# Proximity_sensor_v1.net
KiCad netlist of a schematic drawn in EAGLE
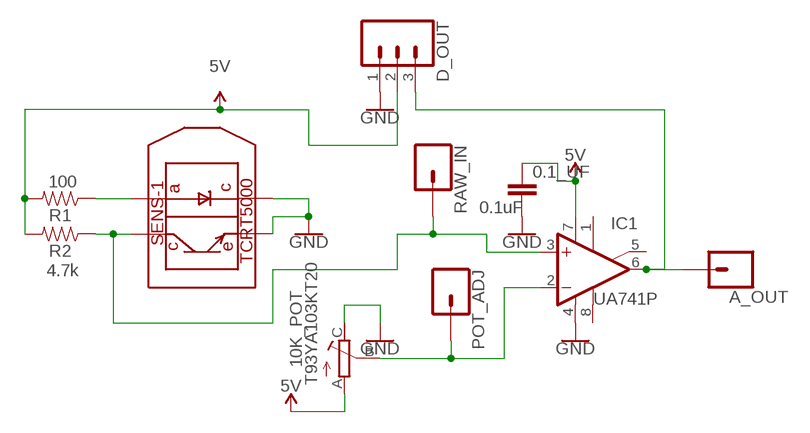
[diagram p0: schematic, sheet 1]

(export (version "E")
  (design (tool "Eeschema 10.0.6"))
  (components
    (comp (ref "0.1_UF")
      (value "0.1uF")
      (footprint "eagle-import:CAP-PTH-SMALL-KIT")
      (libsource (lib "eagle-import") (part "0.1UF-KIT-EZ-50V-20%"))
    )
    (comp (ref "10K_POT")
      (value "T93YA103KT20")
      (footprint "eagle-import:TRIM_T93YA103KT20")
      (fields (field (name "DIGI-KEY_PART_NUMBER") "T93YA-10K-ND") (field (name "MF") "Vishay"))
      (libsource (lib "eagle-import") (part "T93YA103KT20"))
    )
    (comp (ref "A_OUT")
      (value "CONN_01")
      (footprint "eagle-import:1X01")
      (libsource (lib "eagle-import") (part "CONN_01"))
    )
    (comp (ref "D_OUT")
      (value "CONN_03")
      (footprint "eagle-import:1X03")
      (libsource (lib "eagle-import") (part "CONN_03"))
    )
    (comp (ref "IC1")
      (value "UA741P")
      (footprint "eagle-import:DIL08")
      (libsource (lib "eagle-import") (part "741PUA"))
    )
    (comp (ref "POT_ADJ")
      (value "CONN_01")
      (footprint "eagle-import:1X01")
      (libsource (lib "eagle-import") (part "CONN_01"))
    )
    (comp (ref "R1")
      (value "100")
      (footprint "eagle-import:AXIAL-0.3-KIT")
      (libsource (lib "eagle-import") (part "RESISTORAXIAL-0.3-KIT"))
    )
    (comp (ref "R2")
      (value "4.7k")
      (footprint "eagle-import:AXIAL-0.3-KIT")
      (libsource (lib "eagle-import") (part "RESISTORAXIAL-0.3-KIT"))
    )
    (comp (ref "RAW_IN")
      (value "CONN_01")
      (footprint "eagle-import:1X01")
      (libsource (lib "eagle-import") (part "CONN_01"))
    )
    (comp (ref "SENS-1")
      (value "TCRT5000")
      (footprint "eagle-import:5000")
      (libsource (lib "eagle-import") (part "TCRT5000"))
    )
  )
  (nets
    (net (code "1") (name "5V") (class "Default")
      (node (ref "0.1_UF") (pin "1") (pinfunction "1_1") (pintype "passive"))
      (node (ref "10K_POT") (pin "A") (pinfunction "A_A") (pintype "passive"))
      (node (ref "D_OUT") (pin "2") (pinfunction "2_2") (pintype "passive"))
      (node (ref "IC1") (pin "7") (pinfunction "V+_7") (pintype "power_in"))
      (node (ref "R1") (pin "P$2") (pinfunction "2_P$2") (pintype "passive"))
      (node (ref "R2") (pin "P$2") (pinfunction "2_P$2") (pintype "passive"))
    )
    (net (code "2") (name "GND") (class "Default")
      (node (ref "0.1_UF") (pin "2") (pinfunction "2_2") (pintype "passive"))
      (node (ref "10K_POT") (pin "C") (pinfunction "C_C") (pintype "passive"))
      (node (ref "D_OUT") (pin "1") (pinfunction "1_1") (pintype "passive"))
      (node (ref "IC1") (pin "4") (pinfunction "V-_4") (pintype "power_in"))
      (node (ref "SENS-1") (pin "P$2") (pinfunction "P$2_P$2") (pintype "passive"))
      (node (ref "SENS-1") (pin "P$4") (pinfunction "P$4_P$4") (pintype "passive"))
    )
    (net (code "3") (name "Net-(IC1-+IN)") (class "Default")
      (node (ref "IC1") (pin "3") (pinfunction "+IN_3") (pintype "input"))
      (node (ref "R2") (pin "P$1") (pinfunction "1_P$1") (pintype "passive"))
      (node (ref "RAW_IN") (pin "1") (pinfunction "1_1") (pintype "passive"))
      (node (ref "SENS-1") (pin "P$1") (pinfunction "P$1_P$1") (pintype "passive"))
    )
    (net (code "4") (name "Net-(IC1--IN)") (class "Default")
      (node (ref "10K_POT") (pin "B") (pinfunction "B_B") (pintype "passive"))
      (node (ref "IC1") (pin "2") (pinfunction "-IN_2") (pintype "input"))
      (node (ref "POT_ADJ") (pin "1") (pinfunction "1_1") (pintype "passive"))
    )
    (net (code "5") (name "Net-(IC1-OUT)") (class "Default")
      (node (ref "A_OUT") (pin "1") (pinfunction "1_1") (pintype "passive"))
      (node (ref "D_OUT") (pin "3") (pinfunction "3_3") (pintype "passive"))
      (node (ref "IC1") (pin "6") (pinfunction "OUT_6") (pintype "output"))
    )
    (net (code "6") (name "Net-(R1-1)") (class "Default")
      (node (ref "R1") (pin "P$1") (pinfunction "1_P$1") (pintype "passive"))
      (node (ref "SENS-1") (pin "P$3") (pinfunction "P$3_P$3") (pintype "passive"))
    )
    (net (code "7") (name "unconnected-(IC1-ON1-Pad1)") (class "Default")
      (node (ref "IC1") (pin "1") (pinfunction "ON1_1") (pintype "passive"))
    )
    (net (code "8") (name "unconnected-(IC1-ON2-Pad5)") (class "Default")
      (node (ref "IC1") (pin "5") (pinfunction "ON2_5") (pintype "passive"))
    )
    (net (code "9") (name "unconnected-(IC1-OPT-Pad8)") (class "Default")
      (node (ref "IC1") (pin "8") (pinfunction "OPT_8") (pintype "passive"))
    )
  )
)
